# RGB_Encoder_Switcher_v1p1.net
KiCad netlist of a schematic drawn in EAGLE
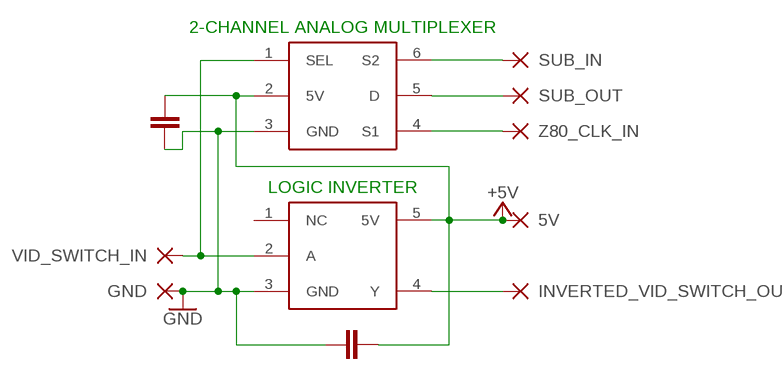
[diagram p0: schematic, sheet 1]

(export (version "E")
  (design (tool "Eeschema 10.0.6"))
  (components
    (comp (ref "5V")
      (value "WIREPADCIRCLE-1,5X1,5")
      (footprint "eagle-import:CIRCLE-1,5X1,5")
      (libsource (lib "eagle-import") (part "WIREPADCIRCLE-1,5X1,5"))
    )
    (comp (ref "C1")
      (value "0.1uF")
      (footprint "eagle-import:C0603")
      (libsource (lib "eagle-import") (part "C-EUC0603"))
    )
    (comp (ref "C2")
      (value "0.1uF")
      (footprint "eagle-import:C0603")
      (libsource (lib "eagle-import") (part "C-EUC0603"))
    )
    (comp (ref "GND")
      (value "WIREPADCIRCLE-1,5X1,5")
      (footprint "eagle-import:CIRCLE-1,5X1,5")
      (libsource (lib "eagle-import") (part "WIREPADCIRCLE-1,5X1,5"))
    )
    (comp (ref "INVERTED_VID_SWITCH_OUT")
      (value "WIREPADCIRCLE-1,5X1,5")
      (footprint "eagle-import:CIRCLE-1,5X1,5")
      (libsource (lib "eagle-import") (part "WIREPADCIRCLE-1,5X1,5"))
    )
    (comp (ref "INVERTER")
      (value "74AHCT1G04DBVRE4")
      (footprint "eagle-import:SOT95P280X110-5N")
      (libsource (lib "eagle-import") (part "74AHCT1G04DBVRE4"))
    )
    (comp (ref "MULTIPLEXER")
      (value "TMUX1219DBVR")
      (footprint "eagle-import:SOT95P280X110-6N")
      (libsource (lib "eagle-import") (part "TMUX1219DBVR"))
    )
    (comp (ref "SUB_IN")
      (value "WIREPADCIRCLE-1,5X1,5")
      (footprint "eagle-import:CIRCLE-1,5X1,5")
      (libsource (lib "eagle-import") (part "WIREPADCIRCLE-1,5X1,5"))
    )
    (comp (ref "SUB_OUT")
      (value "WIREPADCIRCLE-1,5X1,5")
      (footprint "eagle-import:CIRCLE-1,5X1,5")
      (libsource (lib "eagle-import") (part "WIREPADCIRCLE-1,5X1,5"))
    )
    (comp (ref "VID_SWITCH_IN")
      (value "WIREPADCIRCLE-1,5X1,5")
      (footprint "eagle-import:CIRCLE-1,5X1,5")
      (libsource (lib "eagle-import") (part "WIREPADCIRCLE-1,5X1,5"))
    )
    (comp (ref "Z80_CLK_IN")
      (value "WIREPADCIRCLE-1,5X1,5")
      (footprint "eagle-import:CIRCLE-1,5X1,5")
      (libsource (lib "eagle-import") (part "WIREPADCIRCLE-1,5X1,5"))
    )
  )
  (nets
    (net (code "1") (name "+5V") (class "Default")
      (node (ref "5V") (pin "1") (pinfunction "P_1") (pintype "passive"))
      (node (ref "C1") (pin "1") (pinfunction "1_1") (pintype "passive"))
      (node (ref "C2") (pin "2") (pinfunction "2_2") (pintype "passive"))
      (node (ref "INVERTER") (pin "5") (pinfunction "5V_5") (pintype "bidirectional"))
      (node (ref "MULTIPLEXER") (pin "2") (pinfunction "5V_2") (pintype "power_in"))
    )
    (net (code "2") (name "GND") (class "Default")
      (node (ref "C1") (pin "2") (pinfunction "2_2") (pintype "passive"))
      (node (ref "C2") (pin "1") (pinfunction "1_1") (pintype "passive"))
      (node (ref "GND") (pin "1") (pinfunction "P_1") (pintype "passive"))
      (node (ref "INVERTER") (pin "3") (pinfunction "GND_3") (pintype "bidirectional"))
      (node (ref "MULTIPLEXER") (pin "3") (pinfunction "GND_3") (pintype "power_in"))
    )
    (net (code "3") (name "Net-(INVERTED_VID_SWITCH_OUT-P)") (class "Default")
      (node (ref "INVERTED_VID_SWITCH_OUT") (pin "1") (pinfunction "P_1") (pintype "passive"))
      (node (ref "INVERTER") (pin "4") (pinfunction "Y_4") (pintype "output"))
    )
    (net (code "4") (name "Net-(INVERTER-A)") (class "Default")
      (node (ref "INVERTER") (pin "2") (pinfunction "A_2") (pintype "input"))
      (node (ref "MULTIPLEXER") (pin "1") (pinfunction "SEL_1") (pintype "bidirectional"))
      (node (ref "VID_SWITCH_IN") (pin "1") (pinfunction "P_1") (pintype "passive"))
    )
    (net (code "5") (name "Net-(MULTIPLEXER-D)") (class "Default")
      (node (ref "MULTIPLEXER") (pin "5") (pinfunction "D_5") (pintype "bidirectional"))
      (node (ref "SUB_OUT") (pin "1") (pinfunction "P_1") (pintype "passive"))
    )
    (net (code "6") (name "Net-(MULTIPLEXER-S1)") (class "Default")
      (node (ref "MULTIPLEXER") (pin "4") (pinfunction "S1_4") (pintype "bidirectional"))
      (node (ref "Z80_CLK_IN") (pin "1") (pinfunction "P_1") (pintype "passive"))
    )
    (net (code "7") (name "Net-(MULTIPLEXER-S2)") (class "Default")
      (node (ref "MULTIPLEXER") (pin "6") (pinfunction "S2_6") (pintype "bidirectional"))
      (node (ref "SUB_IN") (pin "1") (pinfunction "P_1") (pintype "passive"))
    )
    (net (code "8") (name "unconnected-(INVERTER-NC-Pad1)") (class "Default")
      (node (ref "INVERTER") (pin "1") (pinfunction "NC_1") (pintype "no_connect"))
    )
  )
)
